# AlarmSwitch.net
KiCad netlist of a schematic drawn in Altium Designer
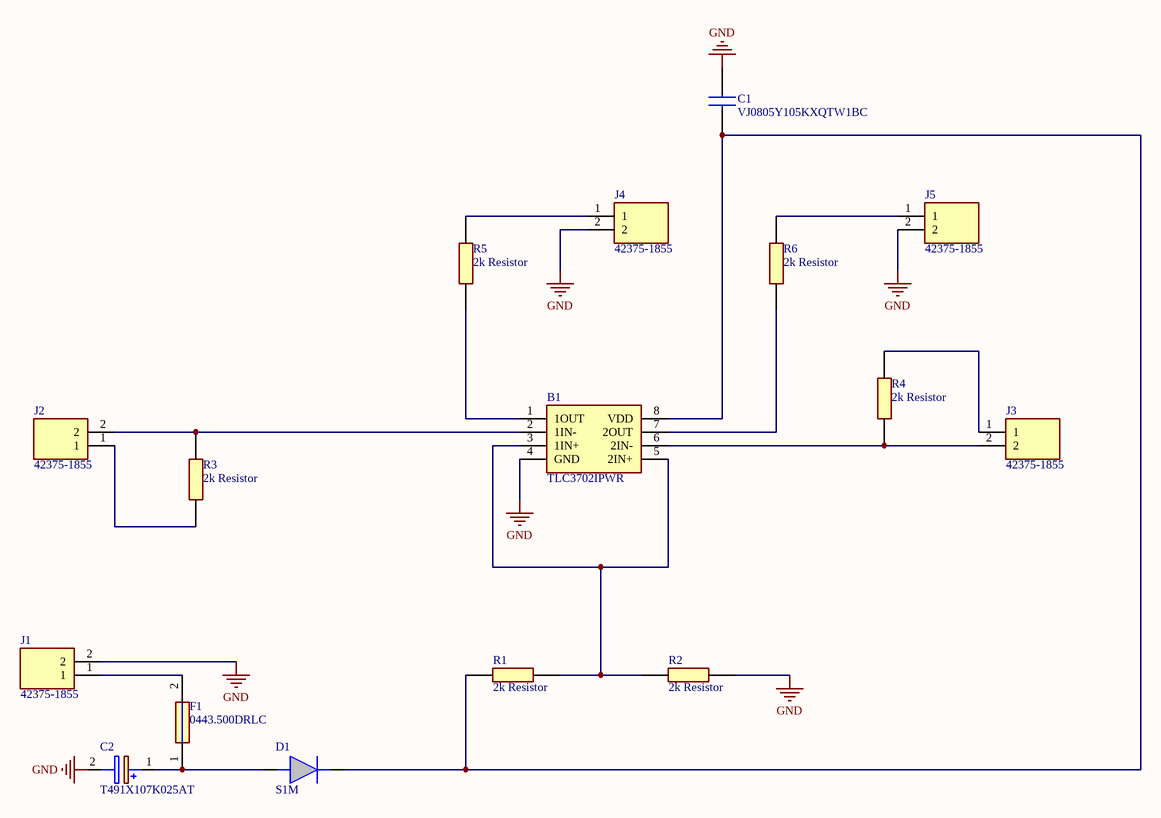
[diagram p0: AlarmSwitch.SchDoc]

(export (version "E")
  (design (tool "Eeschema 10.0.6"))
  (components
    (comp (ref "B1")
      (value "TLC3702IPWR")
      (footprint "SOP65P640X120-8N")
      (description "Texas Instruments TLC3702IPWR Dual Comparator, Push-Pull O/P, 5 V 8-Pin TSSOP")
      (fields (field (name "MOUSER PART NUMBER") "595-TLC3702IPWR"))
      (libsource (lib "TLC3702IPWR") (part "TLC3702IPWR"))
    )
    (comp (ref "C1")
      (value "VJ0805Y105KXQTW1BC")
      (footprint "CAPC2012X135N")
      (description "Multilayer Ceramic Capacitors MLCC - SMD/SMT 0805 1uF 10volts X7R 10%")
      (fields (field (name "MOUSER PART NUMBER") "77-VJ0805Y105KXQTBC"))
      (libsource (lib "VJ0805Y105KXQTW1BC") (part "VJ0805Y105KXQTW1BC"))
    )
    (comp (ref "C2")
      (value "T491X107K025AT")
      (footprint "SamacSys:T491X")
      (description "Capacitor Polarised")
      (fields (field (name "MOUSER PART NUMBER") "80-T491X107K025AT"))
      (libsource (lib "*") (part "T491X107K025AT"))
    )
    (comp (ref "D1")
      (value "S1M")
      (footprint "DIOM5227X270N")
      (description "Glass passivated junction.; Low profile package.")
      (fields (field (name "MOUSER PART NUMBER") "512-S1M"))
      (libsource (lib "S1M") (part "S1M"))
    )
    (comp (ref "F1")
      (value "0443.500DRLC")
      (footprint "SamacSys:0443500DR")
      (description "Fuse")
      (fields (field (name "MOUSER PART NUMBER") "576-0443.500DRLC"))
      (libsource (lib "*") (part "0443.500DRLC"))
    )
    (comp (ref "J1")
      (value "42375-1855")
      (footprint "HDRV2W87P0X254_1X2_768X249X1494P")
      (description "Headers & Wire Housings KK 100 Hdr Assy Bkw 02 Ckt Tin")
      (fields (field (name "MOUSER PART NUMBER") "538-42375-1855"))
      (libsource (lib "") (part "42375-1855_1"))
    )
    (comp (ref "J2")
      (value "42375-1855")
      (footprint "HDRV2W87P0X254_1X2_768X249X1494P")
      (description "Headers & Wire Housings KK 100 Hdr Assy Bkw 02 Ckt Tin")
      (fields (field (name "MOUSER PART NUMBER") "538-42375-1855"))
      (libsource (lib "") (part "42375-1855_1"))
    )
    (comp (ref "J3")
      (value "42375-1855")
      (footprint "HDRV2W87P0X254_1X2_768X249X1494P")
      (description "Headers & Wire Housings KK 100 Hdr Assy Bkw 02 Ckt Tin")
      (fields (field (name "MOUSER PART NUMBER") "538-42375-1855"))
      (libsource (lib "42375-1855") (part "42375-1855"))
    )
    (comp (ref "J4")
      (value "42375-1855")
      (footprint "HDRV2W87P0X254_1X2_768X249X1494P")
      (description "Headers & Wire Housings KK 100 Hdr Assy Bkw 02 Ckt Tin")
      (fields (field (name "MOUSER PART NUMBER") "538-42375-1855"))
      (libsource (lib "42375-1855") (part "42375-1855"))
    )
    (comp (ref "J5")
      (value "42375-1855")
      (footprint "HDRV2W87P0X254_1X2_768X249X1494P")
      (description "Headers & Wire Housings KK 100 Hdr Assy Bkw 02 Ckt Tin")
      (fields (field (name "MOUSER PART NUMBER") "538-42375-1855"))
      (libsource (lib "42375-1855") (part "42375-1855"))
    )
    (comp (ref "R1")
      (value "2k Resistor")
      (footprint "ERA6AEB101V")
      (description "Metal Thin Film Chip Resistor, 0805, 0.125W")
      (fields (field (name "MANUFACTURER_PART_NUMBER") "ERA-6AED4990V"))
      (libsource (lib "") (part "ERA-6AED4990V_1"))
    )
    (comp (ref "R2")
      (value "2k Resistor")
      (footprint "ERA6AEB101V")
      (description "Metal Thin Film Chip Resistor, 0805, 0.125W")
      (fields (field (name "MANUFACTURER_PART_NUMBER") "ERA-6AED4990V"))
      (libsource (lib "") (part "ERA-6AED4990V_1"))
    )
    (comp (ref "R3")
      (value "2k Resistor")
      (footprint "ERA6AEB101V")
      (description "Metal Thin Film Chip Resistor, 0805, 0.125W")
      (fields (field (name "MANUFACTURER_PART_NUMBER") "ERA-6AED4990V"))
      (libsource (lib "ERA-6AED4990V") (part "ERA-6AED4990V"))
    )
    (comp (ref "R4")
      (value "2k Resistor")
      (footprint "ERA6AEB101V")
      (description "Metal Thin Film Chip Resistor, 0805, 0.125W")
      (fields (field (name "MANUFACTURER_PART_NUMBER") "ERA-6AED4990V"))
      (libsource (lib "ERA-6AED4990V") (part "ERA-6AED4990V"))
    )
    (comp (ref "R5")
      (value "2k Resistor")
      (footprint "ERA6AEB101V")
      (description "Metal Thin Film Chip Resistor, 0805, 0.125W")
      (fields (field (name "MANUFACTURER_PART_NUMBER") "ERA-6AED4990V"))
      (libsource (lib "ERA-6AED4990V") (part "ERA-6AED4990V"))
    )
    (comp (ref "R6")
      (value "2k Resistor")
      (footprint "ERA6AEB101V")
      (description "Metal Thin Film Chip Resistor, 0805, 0.125W")
      (fields (field (name "MANUFACTURER_PART_NUMBER") "ERA-6AED4990V"))
      (libsource (lib "ERA-6AED4990V") (part "ERA-6AED4990V"))
    )
  )
  (nets
    (net (code "1") (name "GND") (class "Default")
      (node (ref "B1") (pin "4") (pinfunction "GND_4") (pintype "passive"))
      (node (ref "C1") (pin "2") (pinfunction "2_2") (pintype "passive"))
      (node (ref "C2") (pin "2") (pinfunction "-_2") (pintype "passive"))
      (node (ref "J1") (pin "2") (pinfunction "2_2") (pintype "passive"))
      (node (ref "J4") (pin "2") (pinfunction "2_2") (pintype "passive"))
      (node (ref "J5") (pin "2") (pinfunction "2_2") (pintype "passive"))
      (node (ref "R2") (pin "2") (pinfunction "2_2") (pintype "passive"))
    )
    (net (code "2") (name "Net-(B1-1IN+)") (class "Default")
      (node (ref "B1") (pin "3") (pinfunction "1IN+_3") (pintype "passive"))
      (node (ref "B1") (pin "5") (pinfunction "2IN+_5") (pintype "passive"))
      (node (ref "R1") (pin "2") (pinfunction "2_2") (pintype "passive"))
      (node (ref "R2") (pin "1") (pinfunction "1_1") (pintype "passive"))
    )
    (net (code "3") (name "Net-(B1-1IN-)") (class "Default")
      (node (ref "B1") (pin "2") (pinfunction "1IN-_2") (pintype "passive"))
      (node (ref "J2") (pin "2") (pinfunction "2_2") (pintype "passive"))
      (node (ref "R3") (pin "2") (pinfunction "2_2") (pintype "passive"))
    )
    (net (code "4") (name "Net-(B1-1OUT)") (class "Default")
      (node (ref "B1") (pin "1") (pinfunction "1OUT_1") (pintype "passive"))
      (node (ref "R5") (pin "1") (pinfunction "1_1") (pintype "passive"))
    )
    (net (code "5") (name "Net-(B1-2IN-)") (class "Default")
      (node (ref "B1") (pin "6") (pinfunction "2IN-_6") (pintype "passive"))
      (node (ref "J3") (pin "2") (pinfunction "2_2") (pintype "passive"))
      (node (ref "R4") (pin "1") (pinfunction "1_1") (pintype "passive"))
    )
    (net (code "6") (name "Net-(B1-2OUT)") (class "Default")
      (node (ref "B1") (pin "7") (pinfunction "2OUT_7") (pintype "passive"))
      (node (ref "R6") (pin "1") (pinfunction "1_1") (pintype "passive"))
    )
    (net (code "7") (name "Net-(B1-VDD)") (class "Default")
      (node (ref "B1") (pin "8") (pinfunction "VDD_8") (pintype "passive"))
      (node (ref "C1") (pin "1") (pinfunction "1_1") (pintype "passive"))
      (node (ref "D1") (pin "1") (pinfunction "K_1") (pintype "passive"))
      (node (ref "R1") (pin "1") (pinfunction "1_1") (pintype "passive"))
    )
    (net (code "8") (name "Net-(C2-+)") (class "Default")
      (node (ref "C2") (pin "1") (pinfunction "+_1") (pintype "passive"))
      (node (ref "D1") (pin "2") (pinfunction "A_2") (pintype "passive"))
      (node (ref "F1") (pin "1") (pinfunction "1_1") (pintype "passive"))
    )
    (net (code "9") (name "Net-(F1-Pad2)") (class "Default")
      (node (ref "F1") (pin "2") (pinfunction "2_2") (pintype "passive"))
      (node (ref "J1") (pin "1") (pinfunction "1_1") (pintype "passive"))
    )
    (net (code "10") (name "Net-(J2-Pad1)") (class "Default")
      (node (ref "J2") (pin "1") (pinfunction "1_1") (pintype "passive"))
      (node (ref "R3") (pin "1") (pinfunction "1_1") (pintype "passive"))
    )
    (net (code "11") (name "Net-(J3-Pad1)") (class "Default")
      (node (ref "J3") (pin "1") (pinfunction "1_1") (pintype "passive"))
      (node (ref "R4") (pin "2") (pinfunction "2_2") (pintype "passive"))
    )
    (net (code "12") (name "Net-(J4-Pad1)") (class "Default")
      (node (ref "J4") (pin "1") (pinfunction "1_1") (pintype "passive"))
      (node (ref "R5") (pin "2") (pinfunction "2_2") (pintype "passive"))
    )
    (net (code "13") (name "Net-(J5-Pad1)") (class "Default")
      (node (ref "J5") (pin "1") (pinfunction "1_1") (pintype "passive"))
      (node (ref "R6") (pin "2") (pinfunction "2_2") (pintype "passive"))
    )
  )
)
